# Receiver.net
KiCad netlist of a schematic drawn in EAGLE
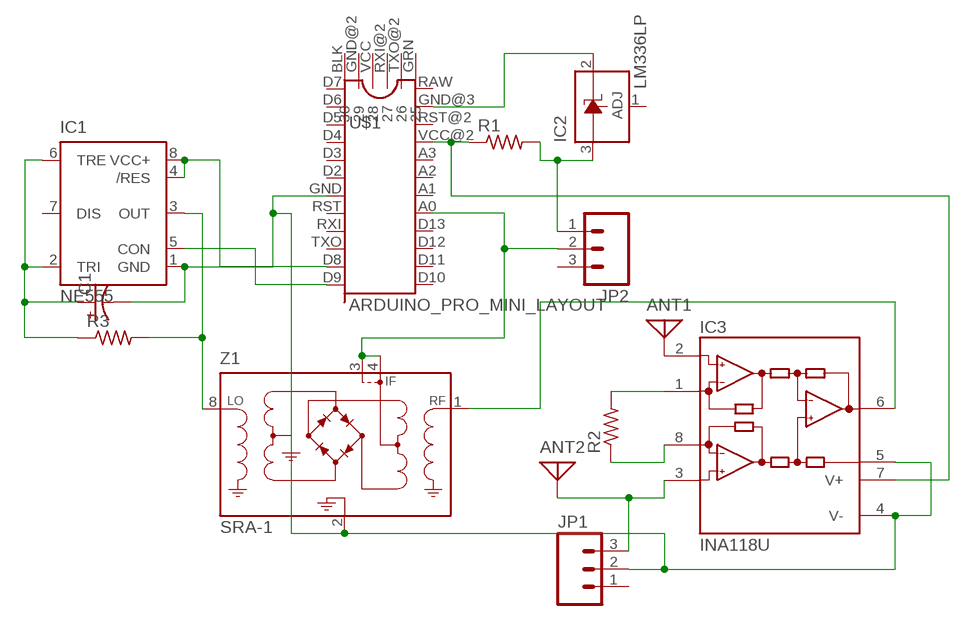
[diagram p0: schematic, sheet 1]

(export (version "E")
  (design (tool "Eeschema 10.0.6"))
  (components
    (comp (ref "ANT1")
      (value "ANTENNA")
      (footprint "eagle-import:PAD-01")
      (libsource (lib "eagle-import") (part "ANTENNA"))
    )
    (comp (ref "ANT2")
      (value "ANTENNA")
      (footprint "eagle-import:PAD-01")
      (libsource (lib "eagle-import") (part "ANTENNA"))
    )
    (comp (ref "C1")
      (value "CPOL-USE2,5-6E")
      (footprint "eagle-import:E2,5-6E")
      (libsource (lib "eagle-import") (part "CPOL-USE2,5-6E"))
    )
    (comp (ref "IC1")
      (value "NE555")
      (footprint "eagle-import:DIL-08")
      (fields (field (name "MF") "Arrow Electronics") (field (name "MPN") "NE555N"))
      (libsource (lib "eagle-import") (part "NE555"))
    )
    (comp (ref "IC2")
      (value "LM336LP")
      (footprint "eagle-import:TO92")
      (libsource (lib "eagle-import") (part "LM336LP"))
    )
    (comp (ref "IC3")
      (value "INA118U")
      (footprint "eagle-import:SO08")
      (fields (field (name "MF") "TEXAS INSTRUMENTS"))
      (libsource (lib "eagle-import") (part "INA118U"))
    )
    (comp (ref "JP1")
      (value "M03PTH")
      (footprint "eagle-import:1X03")
      (libsource (lib "eagle-import") (part "M03PTH"))
    )
    (comp (ref "JP2")
      (value "M03PTH")
      (footprint "eagle-import:1X03")
      (libsource (lib "eagle-import") (part "M03PTH"))
    )
    (comp (ref "R1")
      (value "R-US_0204/5")
      (footprint "eagle-import:0204_5")
      (libsource (lib "eagle-import") (part "R-US_0204/5"))
    )
    (comp (ref "R2")
      (value "R-US_0204/5")
      (footprint "eagle-import:0204_5")
      (libsource (lib "eagle-import") (part "R-US_0204/5"))
    )
    (comp (ref "R3")
      (value "R-US_0204/5")
      (footprint "eagle-import:0204_5")
      (libsource (lib "eagle-import") (part "R-US_0204/5"))
    )
    (comp (ref "U$1")
      (value "ARDUINO_PRO_MINI_LAYOUT")
      (footprint "eagle-import:ARDUINO_PRO_MINI_PINOUT")
      (libsource (lib "eagle-import") (part "ARDUINO_PRO_MINI_LAYOUT"))
    )
    (comp (ref "Z1")
      (value "SRA-1")
      (footprint "eagle-import:A01")
      (libsource (lib "eagle-import") (part "SRA-1"))
    )
  )
  (nets
    (net (code "1") (name "Net-(IC1-CON)") (class "Default")
      (node (ref "IC1") (pin "5") (pinfunction "CON_5") (pintype "input"))
      (node (ref "U$1") (pin "D9") (pinfunction "12_D9") (pintype "passive"))
    )
    (net (code "2") (name "Net-(IC1-GND)") (class "Default")
      (node (ref "C1") (pin "-") (pinfunction "-_-") (pintype "passive"))
      (node (ref "IC1") (pin "1") (pinfunction "GND_1") (pintype "power_in"))
      (node (ref "IC3") (pin "4") (pinfunction "V-_4") (pintype "power_in"))
      (node (ref "IC3") (pin "5") (pinfunction "REF_5") (pintype "passive"))
      (node (ref "JP1") (pin "2") (pinfunction "2_2") (pintype "passive"))
      (node (ref "U$1") (pin "GND") (pinfunction "7_GND") (pintype "passive"))
      (node (ref "Z1") (pin "2") (pinfunction "CASEGROUND_2") (pintype "passive"))
    )
    (net (code "3") (name "Net-(IC1-OUT)") (class "Default")
      (node (ref "IC1") (pin "3") (pinfunction "OUT_3") (pintype "output"))
      (node (ref "R3") (pin "2") (pinfunction "2_2") (pintype "passive"))
      (node (ref "Z1") (pin "8") (pinfunction "L_8") (pintype "passive"))
    )
    (net (code "4") (name "Net-(IC1-TRE)") (class "Default")
      (node (ref "C1") (pin "+") (pinfunction "+_+") (pintype "passive"))
      (node (ref "IC1") (pin "2") (pinfunction "TRI_2") (pintype "input"))
      (node (ref "IC1") (pin "6") (pinfunction "TRE_6") (pintype "input"))
      (node (ref "R3") (pin "1") (pinfunction "1_1") (pintype "passive"))
    )
    (net (code "5") (name "Net-(IC1-VCC+)") (class "Default")
      (node (ref "IC1") (pin "4") (pinfunction "/RES_4") (pintype "input"))
      (node (ref "IC1") (pin "8") (pinfunction "VCC+_8") (pintype "power_in"))
      (node (ref "U$1") (pin "D8") (pinfunction "11_D8") (pintype "passive"))
    )
    (net (code "6") (name "Net-(IC2-A)") (class "Default")
      (node (ref "IC2") (pin "3") (pinfunction "A_3") (pintype "input"))
      (node (ref "JP2") (pin "1") (pinfunction "1_1") (pintype "passive"))
      (node (ref "R1") (pin "2") (pinfunction "2_2") (pintype "passive"))
    )
    (net (code "7") (name "Net-(IC2-C)") (class "Default")
      (node (ref "IC2") (pin "2") (pinfunction "C_2") (pintype "passive"))
      (node (ref "U$1") (pin "GND@3") (pinfunction "23_GND@3") (pintype "passive"))
    )
    (net (code "8") (name "Net-(IC3-+IN)") (class "Default")
      (node (ref "ANT2") (pin "1") (pinfunction "1_1") (pintype "output"))
      (node (ref "IC3") (pin "3") (pinfunction "+IN_3") (pintype "input"))
      (node (ref "JP1") (pin "3") (pinfunction "3_3") (pintype "passive"))
    )
    (net (code "9") (name "Net-(IC3--IN)") (class "Default")
      (node (ref "ANT1") (pin "1") (pinfunction "1_1") (pintype "output"))
      (node (ref "IC3") (pin "2") (pinfunction "-IN_2") (pintype "input"))
    )
    (net (code "10") (name "Net-(IC3-OUT)") (class "Default")
      (node (ref "IC3") (pin "6") (pinfunction "OUT_6") (pintype "output"))
      (node (ref "Z1") (pin "1") (pinfunction "R_1") (pintype "passive"))
    )
    (net (code "11") (name "Net-(IC3-RG-Pad1)") (class "Default")
      (node (ref "IC3") (pin "1") (pinfunction "RG_1") (pintype "passive"))
      (node (ref "R2") (pin "2") (pinfunction "2_2") (pintype "passive"))
    )
    (net (code "12") (name "Net-(IC3-RG-Pad8)") (class "Default")
      (node (ref "IC3") (pin "8") (pinfunction "RG_8") (pintype "passive"))
      (node (ref "R2") (pin "1") (pinfunction "1_1") (pintype "passive"))
    )
    (net (code "13") (name "Net-(IC3-V+)") (class "Default")
      (node (ref "IC3") (pin "7") (pinfunction "V+_7") (pintype "power_in"))
      (node (ref "R1") (pin "1") (pinfunction "1_1") (pintype "passive"))
      (node (ref "U$1") (pin "VCC@2") (pinfunction "21_VCC@2") (pintype "passive"))
    )
    (net (code "14") (name "Net-(U$1-17)") (class "Default")
      (node (ref "JP2") (pin "2") (pinfunction "2_2") (pintype "passive"))
      (node (ref "U$1") (pin "A0") (pinfunction "17_A0") (pintype "passive"))
      (node (ref "Z1") (pin "3") (pinfunction "IF_3") (pintype "passive"))
      (node (ref "Z1") (pin "4") (pinfunction "IF_4") (pintype "passive"))
    )
    (net (code "15") (name "unconnected-(IC1-DIS-Pad7)") (class "Default")
      (node (ref "IC1") (pin "7") (pinfunction "DIS_7") (pintype "input"))
    )
    (net (code "16") (name "unconnected-(IC2-ADJ-Pad1)") (class "Default")
      (node (ref "IC2") (pin "1") (pinfunction "ADJ_1") (pintype "input"))
    )
    (net (code "17") (name "unconnected-(JP1-Pad1)") (class "Default")
      (node (ref "JP1") (pin "1") (pinfunction "1_1") (pintype "passive"))
    )
    (net (code "18") (name "unconnected-(JP2-Pad3)") (class "Default")
      (node (ref "JP2") (pin "3") (pinfunction "3_3") (pintype "passive"))
    )
    (net (code "19") (name "unconnected-(U$1-1-PadD7)") (class "Default")
      (node (ref "U$1") (pin "D7") (pinfunction "1_D7") (pintype "passive"))
    )
    (net (code "20") (name "unconnected-(U$1-2-PadD6)") (class "Default")
      (node (ref "U$1") (pin "D6") (pinfunction "2_D6") (pintype "passive"))
    )
    (net (code "21") (name "unconnected-(U$1-3-PadD5)") (class "Default")
      (node (ref "U$1") (pin "D5") (pinfunction "3_D5") (pintype "passive"))
    )
    (net (code "22") (name "unconnected-(U$1-4-PadD4)") (class "Default")
      (node (ref "U$1") (pin "D4") (pinfunction "4_D4") (pintype "passive"))
    )
    (net (code "23") (name "unconnected-(U$1-5-PadD3)") (class "Default")
      (node (ref "U$1") (pin "D3") (pinfunction "5_D3") (pintype "passive"))
    )
    (net (code "24") (name "unconnected-(U$1-6-PadD2)") (class "Default")
      (node (ref "U$1") (pin "D2") (pinfunction "6_D2") (pintype "passive"))
    )
    (net (code "25") (name "unconnected-(U$1-8-PadRST)") (class "Default")
      (node (ref "U$1") (pin "RST") (pinfunction "8_RST") (pintype "passive"))
    )
    (net (code "26") (name "unconnected-(U$1-9-PadRXI)") (class "Default")
      (node (ref "U$1") (pin "RXI") (pinfunction "9_RXI") (pintype "passive"))
    )
    (net (code "27") (name "unconnected-(U$1-10-PadTXO)") (class "Default")
      (node (ref "U$1") (pin "TXO") (pinfunction "10_TXO") (pintype "passive"))
    )
    (net (code "28") (name "unconnected-(U$1-13-PadD10)") (class "Default")
      (node (ref "U$1") (pin "D10") (pinfunction "13_D10") (pintype "passive"))
    )
    (net (code "29") (name "unconnected-(U$1-14-PadD11)") (class "Default")
      (node (ref "U$1") (pin "D11") (pinfunction "14_D11") (pintype "passive"))
    )
    (net (code "30") (name "unconnected-(U$1-15-PadD12)") (class "Default")
      (node (ref "U$1") (pin "D12") (pinfunction "15_D12") (pintype "passive"))
    )
    (net (code "31") (name "unconnected-(U$1-16-PadD13)") (class "Default")
      (node (ref "U$1") (pin "D13") (pinfunction "16_D13") (pintype "passive"))
    )
    (net (code "32") (name "unconnected-(U$1-18-PadA1)") (class "Default")
      (node (ref "U$1") (pin "A1") (pinfunction "18_A1") (pintype "passive"))
    )
    (net (code "33") (name "unconnected-(U$1-19-PadA2)") (class "Default")
      (node (ref "U$1") (pin "A2") (pinfunction "19_A2") (pintype "passive"))
    )
    (net (code "34") (name "unconnected-(U$1-20-PadA3)") (class "Default")
      (node (ref "U$1") (pin "A3") (pinfunction "20_A3") (pintype "passive"))
    )
    (net (code "35") (name "unconnected-(U$1-22-PadRST@2)") (class "Default")
      (node (ref "U$1") (pin "RST@2") (pinfunction "22_RST@2") (pintype "passive"))
    )
    (net (code "36") (name "unconnected-(U$1-24-PadRAW)") (class "Default")
      (node (ref "U$1") (pin "RAW") (pinfunction "24_RAW") (pintype "passive"))
    )
    (net (code "37") (name "unconnected-(U$1-25-PadGRN)") (class "Default")
      (node (ref "U$1") (pin "GRN") (pinfunction "25_GRN") (pintype "bidirectional"))
    )
    (net (code "38") (name "unconnected-(U$1-26-PadTXO@2)") (class "Default")
      (node (ref "U$1") (pin "TXO@2") (pinfunction "26_TXO@2") (pintype "bidirectional"))
    )
    (net (code "39") (name "unconnected-(U$1-27-PadRXI@2)") (class "Default")
      (node (ref "U$1") (pin "RXI@2") (pinfunction "27_RXI@2") (pintype "bidirectional"))
    )
    (net (code "40") (name "unconnected-(U$1-28-PadVCC)") (class "Default")
      (node (ref "U$1") (pin "VCC") (pinfunction "28_VCC") (pintype "bidirectional"))
    )
    (net (code "41") (name "unconnected-(U$1-29-PadGND@2)") (class "Default")
      (node (ref "U$1") (pin "GND@2") (pinfunction "29_GND@2") (pintype "bidirectional"))
    )
    (net (code "42") (name "unconnected-(U$1-30-PadBLK)") (class "Default")
      (node (ref "U$1") (pin "BLK") (pinfunction "30_BLK") (pintype "bidirectional"))
    )
  )
)
